# Vl822.net
KiCad netlist of a schematic drawn in Altium Designer
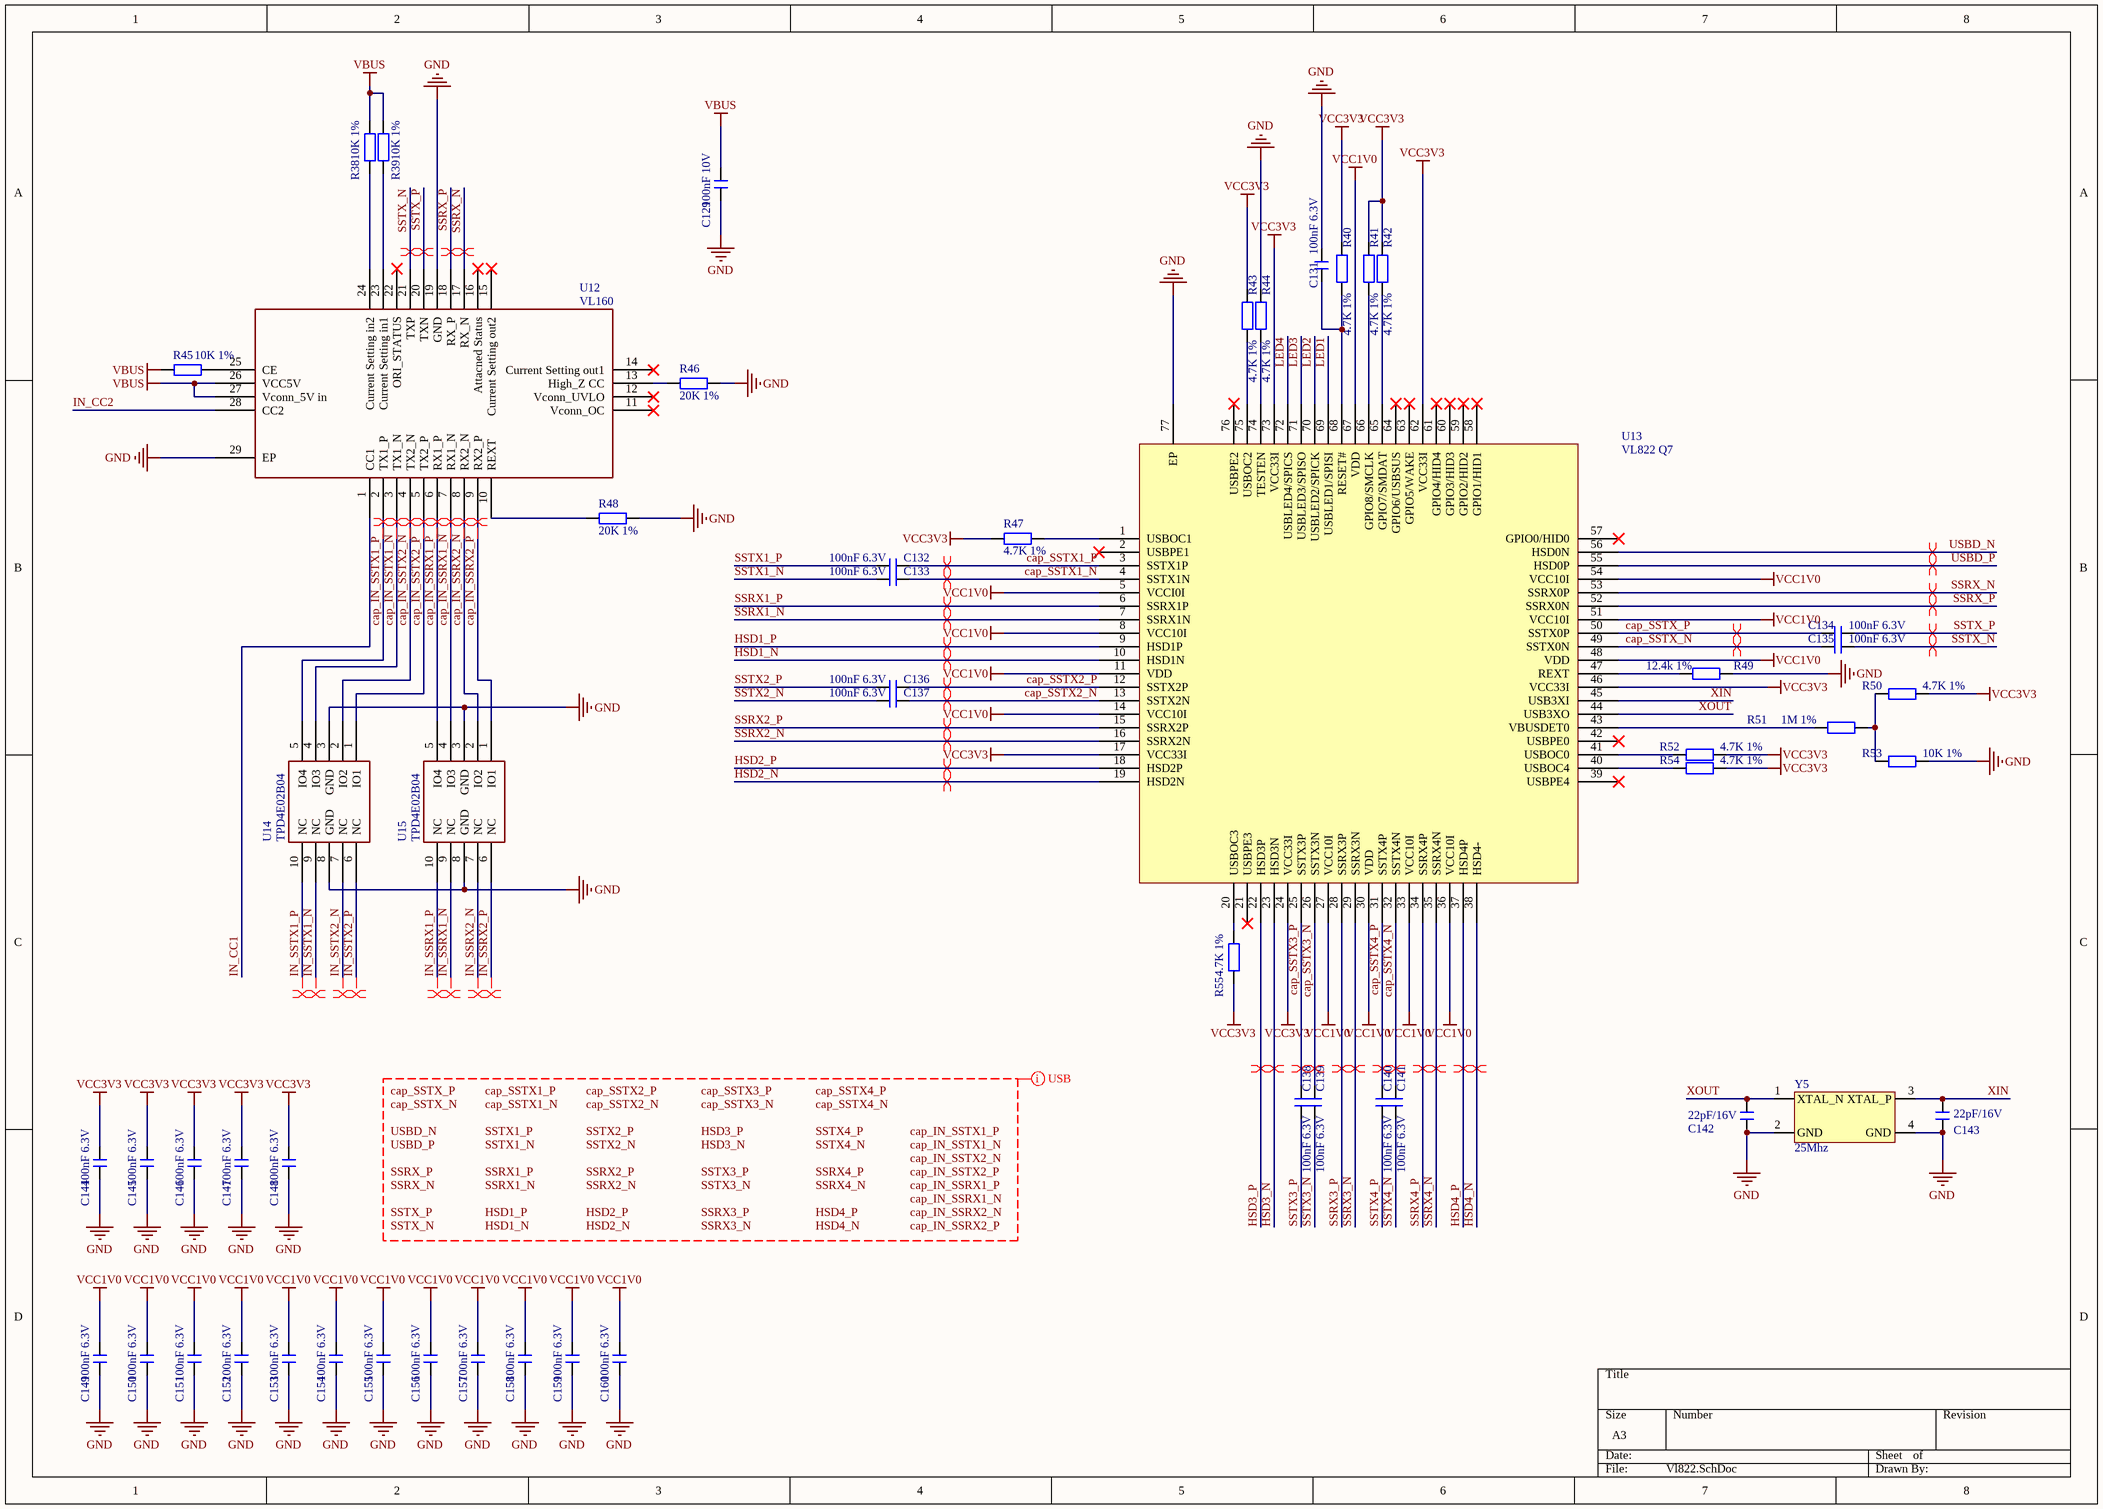
[diagram p0: Vl822.SchDoc]

(export (version "E")
  (design (tool "Eeschema 10.0.6"))
  (components
    (comp (ref "C129")
      (value "100nF 10V")
      (footprint "C0402_L")
      (description "无极性贴片电容")
      (fields (field (name "版权归属") "源创客"))
      (libsource (lib "Capacitor") (part "C"))
    )
    (comp (ref "C131")
      (value "100nF 6.3V")
      (footprint "C0402_L")
      (description "无极性贴片电容")
      (fields (field (name "版权归属") "源创客"))
      (libsource (lib "Capacitor") (part "C"))
    )
    (comp (ref "C132")
      (value "100nF 6.3V")
      (footprint "C0402_L")
      (description "无极性贴片电容")
      (fields (field (name "版权归属") "源创客"))
      (libsource (lib "Capacitor") (part "C"))
    )
    (comp (ref "C133")
      (value "100nF 6.3V")
      (footprint "C0402_L")
      (description "无极性贴片电容")
      (fields (field (name "版权归属") "源创客"))
      (libsource (lib "Capacitor") (part "C"))
    )
    (comp (ref "C134")
      (value "100nF 6.3V")
      (footprint "C0402_L")
      (description "无极性贴片电容")
      (fields (field (name "版权归属") "源创客"))
      (libsource (lib "Capacitor") (part "C"))
    )
    (comp (ref "C135")
      (value "100nF 6.3V")
      (footprint "C0402_L")
      (description "无极性贴片电容")
      (fields (field (name "版权归属") "源创客"))
      (libsource (lib "Capacitor") (part "C"))
    )
    (comp (ref "C136")
      (value "100nF 6.3V")
      (footprint "C0402_L")
      (description "无极性贴片电容")
      (fields (field (name "版权归属") "源创客"))
      (libsource (lib "Capacitor") (part "C"))
    )
    (comp (ref "C137")
      (value "100nF 6.3V")
      (footprint "C0402_L")
      (description "无极性贴片电容")
      (fields (field (name "版权归属") "源创客"))
      (libsource (lib "Capacitor") (part "C"))
    )
    (comp (ref "C138")
      (value "100nF 6.3V")
      (footprint "C0402_L")
      (description "无极性贴片电容")
      (fields (field (name "版权归属") "源创客"))
      (libsource (lib "Capacitor") (part "C"))
    )
    (comp (ref "C139")
      (value "100nF 6.3V")
      (footprint "C0402_L")
      (description "无极性贴片电容")
      (fields (field (name "版权归属") "源创客"))
      (libsource (lib "Capacitor") (part "C"))
    )
    (comp (ref "C140")
      (value "100nF 6.3V")
      (footprint "C0402_L")
      (description "无极性贴片电容")
      (fields (field (name "版权归属") "源创客"))
      (libsource (lib "Capacitor") (part "C"))
    )
    (comp (ref "C141")
      (value "100nF 6.3V")
      (footprint "C0402_L")
      (description "无极性贴片电容")
      (fields (field (name "版权归属") "源创客"))
      (libsource (lib "Capacitor") (part "C"))
    )
    (comp (ref "C142")
      (value "22pF/16V")
      (footprint "C0402_L")
      (description "无极性贴片电容")
      (fields (field (name "版权归属") "源创客"))
      (libsource (lib "Capacitor") (part "C"))
    )
    (comp (ref "C143")
      (value "22pF/16V")
      (footprint "C0402_L")
      (description "无极性贴片电容")
      (fields (field (name "版权归属") "源创客"))
      (libsource (lib "Capacitor") (part "C"))
    )
    (comp (ref "C144")
      (value "100nF 6.3V")
      (footprint "C0402_L")
      (description "无极性贴片电容")
      (fields (field (name "版权归属") "源创客"))
      (libsource (lib "Capacitor") (part "C"))
    )
    (comp (ref "C145")
      (value "100nF 6.3V")
      (footprint "C0402_L")
      (description "无极性贴片电容")
      (fields (field (name "版权归属") "源创客"))
      (libsource (lib "Capacitor") (part "C"))
    )
    (comp (ref "C146")
      (value "100nF 6.3V")
      (footprint "C0402_L")
      (description "无极性贴片电容")
      (fields (field (name "版权归属") "源创客"))
      (libsource (lib "Capacitor") (part "C"))
    )
    (comp (ref "C147")
      (value "100nF 6.3V")
      (footprint "C0402_L")
      (description "无极性贴片电容")
      (fields (field (name "版权归属") "源创客"))
      (libsource (lib "Capacitor") (part "C"))
    )
    (comp (ref "C148")
      (value "100nF 6.3V")
      (footprint "C0402_L")
      (description "无极性贴片电容")
      (fields (field (name "版权归属") "源创客"))
      (libsource (lib "Capacitor") (part "C"))
    )
    (comp (ref "C149")
      (value "100nF 6.3V")
      (footprint "C0402_L")
      (description "无极性贴片电容")
      (fields (field (name "版权归属") "源创客"))
      (libsource (lib "Capacitor") (part "C"))
    )
    (comp (ref "C150")
      (value "100nF 6.3V")
      (footprint "C0402_L")
      (description "无极性贴片电容")
      (fields (field (name "版权归属") "源创客"))
      (libsource (lib "Capacitor") (part "C"))
    )
    (comp (ref "C151")
      (value "100nF 6.3V")
      (footprint "C0402_L")
      (description "无极性贴片电容")
      (fields (field (name "版权归属") "源创客"))
      (libsource (lib "Capacitor") (part "C"))
    )
    (comp (ref "C152")
      (value "100nF 6.3V")
      (footprint "C0402_L")
      (description "无极性贴片电容")
      (fields (field (name "版权归属") "源创客"))
      (libsource (lib "Capacitor") (part "C"))
    )
    (comp (ref "C153")
      (value "100nF 6.3V")
      (footprint "C0402_L")
      (description "无极性贴片电容")
      (fields (field (name "版权归属") "源创客"))
      (libsource (lib "Capacitor") (part "C"))
    )
    (comp (ref "C154")
      (value "100nF 6.3V")
      (footprint "C0402_L")
      (description "无极性贴片电容")
      (fields (field (name "版权归属") "源创客"))
      (libsource (lib "Capacitor") (part "C"))
    )
    (comp (ref "C155")
      (value "100nF 6.3V")
      (footprint "C0402_L")
      (description "无极性贴片电容")
      (fields (field (name "版权归属") "源创客"))
      (libsource (lib "Capacitor") (part "C"))
    )
    (comp (ref "C156")
      (value "100nF 6.3V")
      (footprint "C0402_L")
      (description "无极性贴片电容")
      (fields (field (name "版权归属") "源创客"))
      (libsource (lib "Capacitor") (part "C"))
    )
    (comp (ref "C157")
      (value "100nF 6.3V")
      (footprint "C0402_L")
      (description "无极性贴片电容")
      (fields (field (name "版权归属") "源创客"))
      (libsource (lib "Capacitor") (part "C"))
    )
    (comp (ref "C158")
      (value "100nF 6.3V")
      (footprint "C0402_L")
      (description "无极性贴片电容")
      (fields (field (name "版权归属") "源创客"))
      (libsource (lib "Capacitor") (part "C"))
    )
    (comp (ref "C159")
      (value "100nF 6.3V")
      (footprint "C0402_L")
      (description "无极性贴片电容")
      (fields (field (name "版权归属") "源创客"))
      (libsource (lib "Capacitor") (part "C"))
    )
    (comp (ref "C160")
      (value "100nF 6.3V")
      (footprint "C0402_L")
      (description "无极性贴片电容")
      (fields (field (name "版权归属") "源创客"))
      (libsource (lib "Capacitor") (part "C"))
    )
    (comp (ref "R38")
      (value "10K 1%")
      (footprint "R0402_L")
      (description "贴片电阻")
      (fields (field (name "版权归属") "源创客"))
      (libsource (lib "Resistor") (part "R"))
    )
    (comp (ref "R39")
      (value "10K 1%")
      (footprint "R0402_L")
      (description "贴片电阻")
      (fields (field (name "版权归属") "源创客"))
      (libsource (lib "Resistor") (part "R"))
    )
    (comp (ref "R40")
      (value "4.7K 1%")
      (footprint "R0402_L")
      (description "贴片电阻")
      (fields (field (name "版权归属") "源创客"))
      (libsource (lib "Resistor") (part "R"))
    )
    (comp (ref "R41")
      (value "4.7K 1%")
      (footprint "R0402_L")
      (description "贴片电阻")
      (fields (field (name "版权归属") "源创客"))
      (libsource (lib "Resistor") (part "R"))
    )
    (comp (ref "R42")
      (value "4.7K 1%")
      (footprint "R0402_L")
      (description "贴片电阻")
      (fields (field (name "版权归属") "源创客"))
      (libsource (lib "Resistor") (part "R"))
    )
    (comp (ref "R43")
      (value "4.7K 1%")
      (footprint "R0402_L")
      (description "贴片电阻")
      (fields (field (name "版权归属") "源创客"))
      (libsource (lib "Resistor") (part "R"))
    )
    (comp (ref "R44")
      (value "4.7K 1%")
      (footprint "R0402_L")
      (description "贴片电阻")
      (fields (field (name "版权归属") "源创客"))
      (libsource (lib "Resistor") (part "R"))
    )
    (comp (ref "R45")
      (value "10K 1%")
      (footprint "R0402_L")
      (description "贴片电阻")
      (fields (field (name "版权归属") "源创客"))
      (libsource (lib "Resistor") (part "R"))
    )
    (comp (ref "R46")
      (value "20K 1%")
      (footprint "R0402_L")
      (description "贴片电阻")
      (fields (field (name "版权归属") "源创客"))
      (libsource (lib "Resistor") (part "R"))
    )
    (comp (ref "R47")
      (value "4.7K 1%")
      (footprint "R0402_L")
      (description "贴片电阻")
      (fields (field (name "版权归属") "源创客"))
      (libsource (lib "Resistor") (part "R"))
    )
    (comp (ref "R48")
      (value "20K 1%")
      (footprint "R0402_L")
      (description "贴片电阻")
      (fields (field (name "版权归属") "源创客"))
      (libsource (lib "Resistor") (part "R"))
    )
    (comp (ref "R49")
      (value "12.4k 1%")
      (footprint "R0402_L")
      (description "贴片电阻")
      (fields (field (name "版权归属") "源创客"))
      (libsource (lib "Resistor") (part "R"))
    )
    (comp (ref "R50")
      (value "4.7K 1%")
      (footprint "R0402_L")
      (description "贴片电阻")
      (fields (field (name "版权归属") "源创客"))
      (libsource (lib "Resistor") (part "R"))
    )
    (comp (ref "R51")
      (value "1M 1%")
      (footprint "R0402_L")
      (description "贴片电阻")
      (fields (field (name "版权归属") "源创客"))
      (libsource (lib "Resistor") (part "R"))
    )
    (comp (ref "R52")
      (value "4.7K 1%")
      (footprint "R0402_L")
      (description "贴片电阻")
      (fields (field (name "版权归属") "源创客"))
      (libsource (lib "Resistor") (part "R"))
    )
    (comp (ref "R53")
      (value "10K 1%")
      (footprint "R0402_L")
      (description "贴片电阻")
      (fields (field (name "版权归属") "源创客"))
      (libsource (lib "Resistor") (part "R"))
    )
    (comp (ref "R54")
      (value "4.7K 1%")
      (footprint "R0402_L")
      (description "贴片电阻")
      (fields (field (name "版权归属") "源创客"))
      (libsource (lib "Resistor") (part "R"))
    )
    (comp (ref "R55")
      (value "4.7K 1%")
      (footprint "R0402_L")
      (description "贴片电阻")
      (fields (field (name "版权归属") "源创客"))
      (libsource (lib "Resistor") (part "R"))
    )
    (comp (ref "U12")
      (value "VL160")
      (footprint "MQFN-28_L4.5-W3.5-P0.40-BL-EP")
      (libsource (lib "Brage") (part "VL160"))
    )
    (comp (ref "U13")
      (value "VL822 Q7")
      (footprint "QFN-76_L9.0-W9.0-P0.40-EP6.3-TL")
      (libsource (lib "Brage") (part "VL822 Q7"))
    )
    (comp (ref "U14")
      (value "TPD4E02B04")
      (footprint "DIO_TPD4E02B04DQAR")
      (description "ESD")
      (libsource (lib "Diode") (part "TPD4E02B04"))
    )
    (comp (ref "U15")
      (value "TPD4E02B04")
      (footprint "DIO_TPD4E02B04DQAR")
      (description "ESD")
      (libsource (lib "Diode") (part "TPD4E02B04"))
    )
    (comp (ref "Y5") (value "25Mhz") (footprint "OSC 3225-4P") (libsource (lib "Crystal") (part "Crystal")))
  )
  (nets
    (net (code "1") (name "/HSD1_N") (class "Default")
      (node (ref "U13") (pin "10") (pinfunction "HSD1N_10") (pintype "passive"))
    )
    (net (code "2") (name "/HSD1_P") (class "Default")
      (node (ref "U13") (pin "9") (pinfunction "HSD1P_9") (pintype "passive"))
    )
    (net (code "3") (name "/HSD2_N") (class "Default")
      (node (ref "U13") (pin "19") (pinfunction "HSD2N_19") (pintype "passive"))
    )
    (net (code "4") (name "/HSD2_P") (class "Default")
      (node (ref "U13") (pin "18") (pinfunction "HSD2P_18") (pintype "passive"))
    )
    (net (code "5") (name "/HSD3_N") (class "Default")
      (node (ref "U13") (pin "23") (pinfunction "HSD3N_23") (pintype "passive"))
    )
    (net (code "6") (name "/HSD3_P") (class "Default")
      (node (ref "U13") (pin "22") (pinfunction "HSD3P_22") (pintype "passive"))
    )
    (net (code "7") (name "/HSD4_N") (class "Default")
      (node (ref "U13") (pin "38") (pinfunction "HSD4-_38") (pintype "passive"))
    )
    (net (code "8") (name "/HSD4_P") (class "Default")
      (node (ref "U13") (pin "37") (pinfunction "HSD4P_37") (pintype "passive"))
    )
    (net (code "9") (name "/IN_CC1") (class "Default")
      (node (ref "U12") (pin "1") (pinfunction "CC1_1") (pintype "passive"))
    )
    (net (code "10") (name "/IN_CC2") (class "Default")
      (node (ref "U12") (pin "28") (pinfunction "CC2_28") (pintype "passive"))
    )
    (net (code "11") (name "/IN_SSRX1_N") (class "Default")
      (node (ref "U15") (pin "9") (pinfunction "NC_9") (pintype "passive"))
    )
    (net (code "12") (name "/IN_SSRX1_P") (class "Default")
      (node (ref "U15") (pin "10") (pinfunction "NC_10") (pintype "passive"))
    )
    (net (code "13") (name "/IN_SSRX2_N") (class "Default")
      (node (ref "U15") (pin "7") (pinfunction "NC_7") (pintype "passive"))
    )
    (net (code "14") (name "/IN_SSRX2_P") (class "Default")
      (node (ref "U15") (pin "6") (pinfunction "NC_6") (pintype "passive"))
    )
    (net (code "15") (name "/IN_SSTX1_N") (class "Default")
      (node (ref "U14") (pin "9") (pinfunction "NC_9") (pintype "passive"))
    )
    (net (code "16") (name "/IN_SSTX1_P") (class "Default")
      (node (ref "U14") (pin "10") (pinfunction "NC_10") (pintype "passive"))
    )
    (net (code "17") (name "/IN_SSTX2_N") (class "Default")
      (node (ref "U14") (pin "7") (pinfunction "NC_7") (pintype "passive"))
    )
    (net (code "18") (name "/IN_SSTX2_P") (class "Default")
      (node (ref "U14") (pin "6") (pinfunction "NC_6") (pintype "passive"))
    )
    (net (code "19") (name "/LED1") (class "Default")
      (node (ref "U13") (pin "69") (pinfunction "USBLED1/SPISI_69") (pintype "passive"))
    )
    (net (code "20") (name "/LED2") (class "Default")
      (node (ref "U13") (pin "70") (pinfunction "USBLED2/SPICK_70") (pintype "passive"))
    )
    (net (code "21") (name "/LED3") (class "Default")
      (node (ref "U13") (pin "71") (pinfunction "USBLED3/SPISO_71") (pintype "passive"))
    )
    (net (code "22") (name "/LED4") (class "Default")
      (node (ref "U13") (pin "72") (pinfunction "USBLED4/SPICS_72") (pintype "passive"))
    )
    (net (code "23") (name "/SSRX1_N") (class "Default")
      (node (ref "U13") (pin "7") (pinfunction "SSRX1N_7") (pintype "passive"))
    )
    (net (code "24") (name "/SSRX1_P") (class "Default")
      (node (ref "U13") (pin "6") (pinfunction "SSRX1P_6") (pintype "passive"))
    )
    (net (code "25") (name "/SSRX2_N") (class "Default")
      (node (ref "U13") (pin "16") (pinfunction "SSRX2N_16") (pintype "passive"))
    )
    (net (code "26") (name "/SSRX2_P") (class "Default")
      (node (ref "U13") (pin "15") (pinfunction "SSRX2P_15") (pintype "passive"))
    )
    (net (code "27") (name "/SSRX3_N") (class "Default")
      (node (ref "U13") (pin "29") (pinfunction "SSRX3N_29") (pintype "passive"))
    )
    (net (code "28") (name "/SSRX3_P") (class "Default")
      (node (ref "U13") (pin "28") (pinfunction "SSRX3P_28") (pintype "passive"))
    )
    (net (code "29") (name "/SSRX4_N") (class "Default")
      (node (ref "U13") (pin "35") (pinfunction "SSRX4N_35") (pintype "passive"))
    )
    (net (code "30") (name "/SSRX4_P") (class "Default")
      (node (ref "U13") (pin "34") (pinfunction "SSRX4P_34") (pintype "passive"))
    )
    (net (code "31") (name "/SSRX_N") (class "Default")
      (node (ref "U12") (pin "17") (pinfunction "RX_N_17") (pintype "passive"))
      (node (ref "U13") (pin "53") (pinfunction "SSRX0P_53") (pintype "passive"))
    )
    (net (code "32") (name "/SSRX_P") (class "Default")
      (node (ref "U12") (pin "18") (pinfunction "RX_P_18") (pintype "passive"))
      (node (ref "U13") (pin "52") (pinfunction "SSRX0N_52") (pintype "passive"))
    )
    (net (code "33") (name "/SSTX1_N") (class "Default")
      (node (ref "C133") (pin "1") (pinfunction "1_1") (pintype "passive"))
    )
    (net (code "34") (name "/SSTX1_P") (class "Default")
      (node (ref "C132") (pin "1") (pinfunction "1_1") (pintype "passive"))
    )
    (net (code "35") (name "/SSTX2_N") (class "Default")
      (node (ref "C137") (pin "1") (pinfunction "1_1") (pintype "passive"))
    )
    (net (code "36") (name "/SSTX2_P") (class "Default")
      (node (ref "C136") (pin "1") (pinfunction "1_1") (pintype "passive"))
    )
    (net (code "37") (name "/SSTX3_N") (class "Default")
      (node (ref "C139") (pin "1") (pinfunction "1_1") (pintype "passive"))
    )
    (net (code "38") (name "/SSTX3_P") (class "Default")
      (node (ref "C138") (pin "1") (pinfunction "1_1") (pintype "passive"))
    )
    (net (code "39") (name "/SSTX4_N") (class "Default")
      (node (ref "C141") (pin "1") (pinfunction "1_1") (pintype "passive"))
    )
    (net (code "40") (name "/SSTX4_P") (class "Default")
      (node (ref "C140") (pin "1") (pinfunction "1_1") (pintype "passive"))
    )
    (net (code "41") (name "/SSTX_N") (class "Default")
      (node (ref "C135") (pin "1") (pinfunction "1_1") (pintype "passive"))
      (node (ref "U12") (pin "21") (pinfunction "TXP_21") (pintype "passive"))
    )
    (net (code "42") (name "/SSTX_P") (class "Default")
      (node (ref "C134") (pin "1") (pinfunction "1_1") (pintype "passive"))
      (node (ref "U12") (pin "20") (pinfunction "TXN_20") (pintype "passive"))
    )
    (net (code "43") (name "/USBD_N") (class "Default")
      (node (ref "U13") (pin "56") (pinfunction "HSD0N_56") (pintype "passive"))
    )
    (net (code "44") (name "/USBD_P") (class "Default")
      (node (ref "U13") (pin "55") (pinfunction "HSD0P_55") (pintype "passive"))
    )
    (net (code "45") (name "/XIN") (class "Default")
      (node (ref "C143") (pin "1") (pinfunction "1_1") (pintype "passive"))
      (node (ref "U13") (pin "45") (pinfunction "USB3XI_45") (pintype "passive"))
      (node (ref "Y5") (pin "3") (pinfunction "XTAL_P_3") (pintype "passive"))
    )
    (net (code "46") (name "/XOUT") (class "Default")
      (node (ref "C142") (pin "1") (pinfunction "1_1") (pintype "passive"))
      (node (ref "U13") (pin "44") (pinfunction "USB3XO_44") (pintype "passive"))
      (node (ref "Y5") (pin "1") (pinfunction "XTAL_N_1") (pintype "passive"))
    )
    (net (code "47") (name "/cap_IN_SSRX1_N") (class "Default")
      (node (ref "U12") (pin "7") (pinfunction "RX1_N_7") (pintype "passive"))
      (node (ref "U15") (pin "4") (pinfunction "IO3_4") (pintype "passive"))
    )
    (net (code "48") (name "/cap_IN_SSRX1_P") (class "Default")
      (node (ref "U12") (pin "6") (pinfunction "RX1_P_6") (pintype "passive"))
      (node (ref "U15") (pin "5") (pinfunction "IO4_5") (pintype "passive"))
    )
    (net (code "49") (name "/cap_IN_SSRX2_N") (class "Default")
      (node (ref "U12") (pin "8") (pinfunction "RX2_N_8") (pintype "passive"))
      (node (ref "U15") (pin "2") (pinfunction "IO2_2") (pintype "passive"))
    )
    (net (code "50") (name "/cap_IN_SSRX2_P") (class "Default")
      (node (ref "U12") (pin "9") (pinfunction "RX2_P_9") (pintype "passive"))
      (node (ref "U15") (pin "1") (pinfunction "IO1_1") (pintype "passive"))
    )
    (net (code "51") (name "/cap_IN_SSTX1_N") (class "Default")
      (node (ref "U12") (pin "3") (pinfunction "TX1_N_3") (pintype "passive"))
      (node (ref "U14") (pin "4") (pinfunction "IO3_4") (pintype "passive"))
    )
    (net (code "52") (name "/cap_IN_SSTX1_P") (class "Default")
      (node (ref "U12") (pin "2") (pinfunction "TX1_P_2") (pintype "passive"))
      (node (ref "U14") (pin "5") (pinfunction "IO4_5") (pintype "passive"))
    )
    (net (code "53") (name "/cap_IN_SSTX2_N") (class "Default")
      (node (ref "U12") (pin "4") (pinfunction "TX2_N_4") (pintype "passive"))
      (node (ref "U14") (pin "2") (pinfunction "IO2_2") (pintype "passive"))
    )
    (net (code "54") (name "/cap_IN_SSTX2_P") (class "Default")
      (node (ref "U12") (pin "5") (pinfunction "TX2_P_5") (pintype "passive"))
      (node (ref "U14") (pin "1") (pinfunction "IO1_1") (pintype "passive"))
    )
    (net (code "55") (name "/cap_SSTX1_N") (class "Default")
      (node (ref "C133") (pin "2") (pinfunction "2_2") (pintype "passive"))
      (node (ref "U13") (pin "4") (pinfunction "SSTX1N_4") (pintype "passive"))
    )
    (net (code "56") (name "/cap_SSTX1_P") (class "Default")
      (node (ref "C132") (pin "2") (pinfunction "2_2") (pintype "passive"))
      (node (ref "U13") (pin "3") (pinfunction "SSTX1P_3") (pintype "passive"))
    )
    (net (code "57") (name "/cap_SSTX2_N") (class "Default")
      (node (ref "C137") (pin "2") (pinfunction "2_2") (pintype "passive"))
      (node (ref "U13") (pin "13") (pinfunction "SSTX2N_13") (pintype "passive"))
    )
    (net (code "58") (name "/cap_SSTX2_P") (class "Default")
      (node (ref "C136") (pin "2") (pinfunction "2_2") (pintype "passive"))
      (node (ref "U13") (pin "12") (pinfunction "SSTX2P_12") (pintype "passive"))
    )
    (net (code "59") (name "/cap_SSTX3_N") (class "Default")
      (node (ref "C139") (pin "2") (pinfunction "2_2") (pintype "passive"))
      (node (ref "U13") (pin "26") (pinfunction "SSTX3N_26") (pintype "passive"))
    )
    (net (code "60") (name "/cap_SSTX3_P") (class "Default")
      (node (ref "C138") (pin "2") (pinfunction "2_2") (pintype "passive"))
      (node (ref "U13") (pin "25") (pinfunction "SSTX3P_25") (pintype "passive"))
    )
    (net (code "61") (name "/cap_SSTX4_N") (class "Default")
      (node (ref "C141") (pin "2") (pinfunction "2_2") (pintype "passive"))
      (node (ref "U13") (pin "32") (pinfunction "SSTX4N_32") (pintype "passive"))
    )
    (net (code "62") (name "/cap_SSTX4_P") (class "Default")
      (node (ref "C140") (pin "2") (pinfunction "2_2") (pintype "passive"))
      (node (ref "U13") (pin "31") (pinfunction "SSTX4P_31") (pintype "passive"))
    )
    (net (code "63") (name "/cap_SSTX_N") (class "Default")
      (node (ref "C135") (pin "2") (pinfunction "2_2") (pintype "passive"))
      (node (ref "U13") (pin "49") (pinfunction "SSTX0N_49") (pintype "passive"))
    )
    (net (code "64") (name "/cap_SSTX_P") (class "Default")
      (node (ref "C134") (pin "2") (pinfunction "2_2") (pintype "passive"))
      (node (ref "U13") (pin "50") (pinfunction "SSTX0P_50") (pintype "passive"))
    )
    (net (code "65") (name "GND") (class "Default")
      (node (ref "C129") (pin "1") (pinfunction "1_1") (pintype "passive"))
      (node (ref "C131") (pin "2") (pinfunction "2_2") (pintype "passive"))
      (node (ref "C142") (pin "2") (pinfunction "2_2") (pintype "passive"))
      (node (ref "C143") (pin "2") (pinfunction "2_2") (pintype "passive"))
      (node (ref "C144") (pin "1") (pinfunction "1_1") (pintype "passive"))
      (node (ref "C145") (pin "1") (pinfunction "1_1") (pintype "passive"))
      (node (ref "C146") (pin "1") (pinfunction "1_1") (pintype "passive"))
      (node (ref "C147") (pin "1") (pinfunction "1_1") (pintype "passive"))
      (node (ref "C148") (pin "1") (pinfunction "1_1") (pintype "passive"))
      (node (ref "C149") (pin "1") (pinfunction "1_1") (pintype "passive"))
      (node (ref "C150") (pin "1") (pinfunction "1_1") (pintype "passive"))
      (node (ref "C151") (pin "1") (pinfunction "1_1") (pintype "passive"))
      (node (ref "C152") (pin "1") (pinfunction "1_1") (pintype "passive"))
      (node (ref "C153") (pin "1") (pinfunction "1_1") (pintype "passive"))
      (node (ref "C154") (pin "1") (pinfunction "1_1") (pintype "passive"))
      (node (ref "C155") (pin "1") (pinfunction "1_1") (pintype "passive"))
      (node (ref "C156") (pin "1") (pinfunction "1_1") (pintype "passive"))
      (node (ref "C157") (pin "1") (pinfunction "1_1") (pintype "passive"))
      (node (ref "C158") (pin "1") (pinfunction "1_1") (pintype "passive"))
      (node (ref "C159") (pin "1") (pinfunction "1_1") (pintype "passive"))
      (node (ref "C160") (pin "1") (pinfunction "1_1") (pintype "passive"))
      (node (ref "R44") (pin "2") (pinfunction "2_2") (pintype "passive"))
      (node (ref "R46") (pin "1") (pinfunction "1_1") (pintype "passive"))
      (node (ref "R48") (pin "1") (pinfunction "1_1") (pintype "passive"))
      (node (ref "R49") (pin "2") (pinfunction "2_2") (pintype "passive"))
      (node (ref "R53") (pin "2") (pinfunction "2_2") (pintype "passive"))
      (node (ref "U12") (pin "19") (pinfunction "GND_19") (pintype "passive"))
      (node (ref "U12") (pin "29") (pinfunction "EP_29") (pintype "passive"))
      (node (ref "U13") (pin "77") (pinfunction "EP_77") (pintype "passive"))
      (node (ref "U14") (pin "3") (pinfunction "GND_3") (pintype "passive"))
      (node (ref "U14") (pin "8") (pinfunction "GND_8") (pintype "passive"))
      (node (ref "U15") (pin "3") (pinfunction "GND_3") (pintype "passive"))
      (node (ref "U15") (pin "8") (pinfunction "GND_8") (pintype "passive"))
      (node (ref "Y5") (pin "2") (pinfunction "GND_2") (pintype "passive"))
      (node (ref "Y5") (pin "4") (pinfunction "GND_4") (pintype "passive"))
    )
    (net (code "66") (name "Net-(R50-Pad1)") (class "Default")
      (node (ref "R50") (pin "1") (pinfunction "1_1") (pintype "passive"))
      (node (ref "R51") (pin "2") (pinfunction "2_2") (pintype "passive"))
      (node (ref "R53") (pin "1") (pinfunction "1_1") (pintype "passive"))
    )
    (net (code "67") (name "Net-(U12-CE)") (class "Default")
      (node (ref "R45") (pin "1") (pinfunction "1_1") (pintype "passive"))
      (node (ref "U12") (pin "25") (pinfunction "CE_25") (pintype "passive"))
    )
    (net (code "68") (name "Net-(U12-Current_Setting_in1)") (class "Default")
      (node (ref "R39") (pin "2") (pinfunction "2_2") (pintype "passive"))
      (node (ref "U12") (pin "23") (pinfunction "Current_Setting_in1_23") (pintype "passive"))
    )
    (net (code "69") (name "Net-(U12-Current_Setting_in2)") (class "Default")
      (node (ref "R38") (pin "2") (pinfunction "2_2") (pintype "passive"))
      (node (ref "U12") (pin "24") (pinfunction "Current_Setting_in2_24") (pintype "passive"))
    )
    (net (code "70") (name "Net-(U12-High_Z_CC)") (class "Default")
      (node (ref "R46") (pin "2") (pinfunction "2_2") (pintype "passive"))
      (node (ref "U12") (pin "13") (pinfunction "High_Z_CC_13") (pintype "passive"))
    )
    (net (code "71") (name "Net-(U12-REXT)") (class "Default")
      (node (ref "R48") (pin "2") (pinfunction "2_2") (pintype "passive"))
      (node (ref "U12") (pin "10") (pinfunction "REXT_10") (pintype "passive"))
    )
    (net (code "72") (name "Net-(U13-GPIO7{slash}SMDAT)") (class "Default")
      (node (ref "R42") (pin "1") (pinfunction "1_1") (pintype "passive"))
      (node (ref "U13") (pin "65") (pinfunction "GPIO7/SMDAT_65") (pintype "passive"))
    )
    (net (code "73") (name "Net-(U13-GPIO8{slash}SMCLK)") (class "Default")
      (node (ref "R41") (pin "1") (pinfunction "1_1") (pintype "passive"))
      (node (ref "U13") (pin "66") (pinfunction "GPIO8/SMCLK_66") (pintype "passive"))
    )
    (net (code "74") (name "Net-(U13-RESET#)") (class "Default")
      (node (ref "C131") (pin "1") (pinfunction "1_1") (pintype "passive"))
      (node (ref "R40") (pin "1") (pinfunction "1_1") (pintype "passive"))
      (node (ref "U13") (pin "68") (pinfunction "RESET#_68") (pintype "passive"))
    )
    (net (code "75") (name "Net-(U13-REXT)") (class "Default")
      (node (ref "R49") (pin "1") (pinfunction "1_1") (pintype "passive"))
      (node (ref "U13") (pin "47") (pinfunction "REXT_47") (pintype "passive"))
    )
    (net (code "76") (name "Net-(U13-TESTEN)") (class "Default")
      (node (ref "R44") (pin "1") (pinfunction "1_1") (pintype "passive"))
      (node (ref "U13") (pin "74") (pinfunction "TESTEN_74") (pintype "passive"))
    )
    (net (code "77") (name "Net-(U13-USBOC0)") (class "Default")
      (node (ref "R52") (pin "1") (pinfunction "1_1") (pintype "passive"))
      (node (ref "U13") (pin "41") (pinfunction "USBOC0_41") (pintype "passive"))
    )
    (net (code "78") (name "Net-(U13-USBOC1)") (class "Default")
      (node (ref "R47") (pin "1") (pinfunction "1_1") (pintype "passive"))
      (node (ref "U13") (pin "1") (pinfunction "USBOC1_1") (pintype "passive"))
    )
    (net (code "79") (name "Net-(U13-USBOC2)") (class "Default")
      (node (ref "R43") (pin "1") (pinfunction "1_1") (pintype "passive"))
      (node (ref "U13") (pin "75") (pinfunction "USBOC2_75") (pintype "passive"))
    )
    (net (code "80") (name "Net-(U13-USBOC3)") (class "Default")
      (node (ref "R55") (pin "1") (pinfunction "1_1") (pintype "passive"))
      (node (ref "U13") (pin "20") (pinfunction "USBOC3_20") (pintype "passive"))
    )
    (net (code "81") (name "Net-(U13-USBOC4)") (class "Default")
      (node (ref "R54") (pin "1") (pinfunction "1_1") (pintype "passive"))
      (node (ref "U13") (pin "40") (pinfunction "USBOC4_40") (pintype "passive"))
    )
    (net (code "82") (name "Net-(U13-VBUSDET0)") (class "Default")
      (node (ref "R51") (pin "1") (pinfunction "1_1") (pintype "passive"))
      (node (ref "U13") (pin "43") (pinfunction "VBUSDET0_43") (pintype "passive"))
    )
    (net (code "83") (name "VBUS") (class "Default")
      (node (ref "C129") (pin "2") (pinfunction "2_2") (pintype "passive"))
      (node (ref "R38") (pin "1") (pinfunction "1_1") (pintype "passive"))
      (node (ref "R39") (pin "1") (pinfunction "1_1") (pintype "passive"))
      (node (ref "R45") (pin "2") (pinfunction "2_2") (pintype "passive"))
      (node (ref "U12") (pin "26") (pinfunction "VCC5V_26") (pintype "passive"))
      (node (ref "U12") (pin "27") (pinfunction "Vconn_5V_in_27") (pintype "passive"))
    )
    (net (code "84") (name "VCC1V0") (class "Default")
      (node (ref "C149") (pin "2") (pinfunction "2_2") (pintype "passive"))
      (node (ref "C150") (pin "2") (pinfunction "2_2") (pintype "passive"))
      (node (ref "C151") (pin "2") (pinfunction "2_2") (pintype "passive"))
      (node (ref "C152") (pin "2") (pinfunction "2_2") (pintype "passive"))
      (node (ref "C153") (pin "2") (pinfunction "2_2") (pintype "passive"))
      (node (ref "C154") (pin "2") (pinfunction "2_2") (pintype "passive"))
      (node (ref "C155") (pin "2") (pinfunction "2_2") (pintype "passive"))
      (node (ref "C156") (pin "2") (pinfunction "2_2") (pintype "passive"))
      (node (ref "C157") (pin "2") (pinfunction "2_2") (pintype "passive"))
      (node (ref "C158") (pin "2") (pinfunction "2_2") (pintype "passive"))
      (node (ref "C159") (pin "2") (pinfunction "2_2") (pintype "passive"))
      (node (ref "C160") (pin "2") (pinfunction "2_2") (pintype "passive"))
      (node (ref "U13") (pin "11") (pinfunction "VDD_11") (pintype "passive"))
      (node (ref "U13") (pin "14") (pinfunction "VCC10I_14") (pintype "passive"))
      (node (ref "U13") (pin "27") (pinfunction "VCC10I_27") (pintype "passive"))
      (node (ref "U13") (pin "30") (pinfunction "VDD_30") (pintype "passive"))
      (node (ref "U13") (pin "33") (pinfunction "VCC10I_33") (pintype "passive"))
      (node (ref "U13") (pin "36") (pinfunction "VCC10I_36") (pintype "passive"))
      (node (ref "U13") (pin "48") (pinfunction "VDD_48") (pintype "passive"))
      (node (ref "U13") (pin "5") (pinfunction "VCCI0I_5") (pintype "passive"))
      (node (ref "U13") (pin "51") (pinfunction "VCC10I_51") (pintype "passive"))
      (node (ref "U13") (pin "54") (pinfunction "VCC10I_54") (pintype "passive"))
      (node (ref "U13") (pin "67") (pinfunction "VDD_67") (pintype "passive"))
      (node (ref "U13") (pin "8") (pinfunction "VCC10I_8") (pintype "passive"))
    )
    (net (code "85") (name "VCC3V3") (class "Default")
      (node (ref "C144") (pin "2") (pinfunction "2_2") (pintype "passive"))
      (node (ref "C145") (pin "2") (pinfunction "2_2") (pintype "passive"))
      (node (ref "C146") (pin "2") (pinfunction "2_2") (pintype "passive"))
      (node (ref "C147") (pin "2") (pinfunction "2_2") (pintype "passive"))
      (node (ref "C148") (pin "2") (pinfunction "2_2") (pintype "passive"))
      (node (ref "R40") (pin "2") (pinfunction "2_2") (pintype "passive"))
      (node (ref "R41") (pin "2") (pinfunction "2_2") (pintype "passive"))
      (node (ref "R42") (pin "2") (pinfunction "2_2") (pintype "passive"))
      (node (ref "R43") (pin "2") (pinfunction "2_2") (pintype "passive"))
      (node (ref "R47") (pin "2") (pinfunction "2_2") (pintype "passive"))
      (node (ref "R50") (pin "2") (pinfunction "2_2") (pintype "passive"))
      (node (ref "R52") (pin "2") (pinfunction "2_2") (pintype "passive"))
      (node (ref "R54") (pin "2") (pinfunction "2_2") (pintype "passive"))
      (node (ref "R55") (pin "2") (pinfunction "2_2") (pintype "passive"))
      (node (ref "U13") (pin "17") (pinfunction "VCC33I_17") (pintype "passive"))
      (node (ref "U13") (pin "24") (pinfunction "VCC33I_24") (pintype "passive"))
      (node (ref "U13") (pin "46") (pinfunction "VCC33I_46") (pintype "passive"))
      (node (ref "U13") (pin "62") (pinfunction "VCC33I_62") (pintype "passive"))
      (node (ref "U13") (pin "73") (pinfunction "VCC33I_73") (pintype "passive"))
    )
    (net (code "86") (name "unconnected-(U12-Attacned_Status-Pad16)") (class "Default")
      (node (ref "U12") (pin "16") (pinfunction "Attacned_Status_16") (pintype "passive+no_connect"))
    )
    (net (code "87") (name "unconnected-(U12-Current_Setting_out1-Pad14)") (class "Default")
      (node (ref "U12") (pin "14") (pinfunction "Current_Setting_out1_14") (pintype "passive+no_connect"))
    )
    (net (code "88") (name "unconnected-(U12-Current_Setting_out2-Pad15)") (class "Default")
      (node (ref "U12") (pin "15") (pinfunction "Current_Setting_out2_15") (pintype "passive+no_connect"))
    )
    (net (code "89") (name "unconnected-(U12-ORI_STATUS-Pad22)") (class "Default")
      (node (ref "U12") (pin "22") (pinfunction "ORI_STATUS_22") (pintype "passive+no_connect"))
    )
    (net (code "90") (name "unconnected-(U12-Vconn_OC-Pad11)") (class "Default")
      (node (ref "U12") (pin "11") (pinfunction "Vconn_OC_11") (pintype "passive+no_connect"))
    )
    (net (code "91") (name "unconnected-(U12-Vconn_UVLO-Pad12)") (class "Default")
      (node (ref "U12") (pin "12") (pinfunction "Vconn_UVLO_12") (pintype "passive+no_connect"))
    )
    (net (code "92") (name "unconnected-(U13-GPIO0{slash}HID0-Pad57)") (class "Default")
      (node (ref "U13") (pin "57") (pinfunction "GPIO0/HID0_57") (pintype "passive+no_connect"))
    )
    (net (code "93") (name "unconnected-(U13-GPIO1{slash}HID1-Pad58)") (class "Default")
      (node (ref "U13") (pin "58") (pinfunction "GPIO1/HID1_58") (pintype "passive+no_connect"))
    )
    (net (code "94") (name "unconnected-(U13-GPIO2{slash}HID2-Pad59)") (class "Default")
      (node (ref "U13") (pin "59") (pinfunction "GPIO2/HID2_59") (pintype "passive+no_connect"))
    )
    (net (code "95") (name "unconnected-(U13-GPIO3{slash}HID3-Pad60)") (class "Default")
      (node (ref "U13") (pin "60") (pinfunction "GPIO3/HID3_60") (pintype "passive+no_connect"))
    )
    (net (code "96") (name "unconnected-(U13-GPIO4{slash}HID4-Pad61)") (class "Default")
      (node (ref "U13") (pin "61") (pinfunction "GPIO4/HID4_61") (pintype "passive+no_connect"))
    )
    (net (code "97") (name "unconnected-(U13-GPIO5{slash}WAKE-Pad63)") (class "Default")
      (node (ref "U13") (pin "63") (pinfunction "GPIO5/WAKE_63") (pintype "passive+no_connect"))
    )
    (net (code "98") (name "unconnected-(U13-GPIO6{slash}USBSUS-Pad64)") (class "Default")
      (node (ref "U13") (pin "64") (pinfunction "GPIO6/USBSUS_64") (pintype "passive+no_connect"))
    )
    (net (code "99") (name "unconnected-(U13-USBPE0-Pad42)") (class "Default")
      (node (ref "U13") (pin "42") (pinfunction "USBPE0_42") (pintype "passive+no_connect"))
    )
    (net (code "100") (name "unconnected-(U13-USBPE1-Pad2)") (class "Default")
      (node (ref "U13") (pin "2") (pinfunction "USBPE1_2") (pintype "passive+no_connect"))
    )
    (net (code "101") (name "unconnected-(U13-USBPE2-Pad76)") (class "Default")
      (node (ref "U13") (pin "76") (pinfunction "USBPE2_76") (pintype "passive+no_connect"))
    )
    (net (code "102") (name "unconnected-(U13-USBPE3-Pad21)") (class "Default")
      (node (ref "U13") (pin "21") (pinfunction "USBPE3_21") (pintype "passive+no_connect"))
    )
    (net (code "103") (name "unconnected-(U13-USBPE4-Pad39)") (class "Default")
      (node (ref "U13") (pin "39") (pinfunction "USBPE4_39") (pintype "passive+no_connect"))
    )
  )
)
